# MAIN.net
KiCad netlist of a schematic drawn in EAGLE
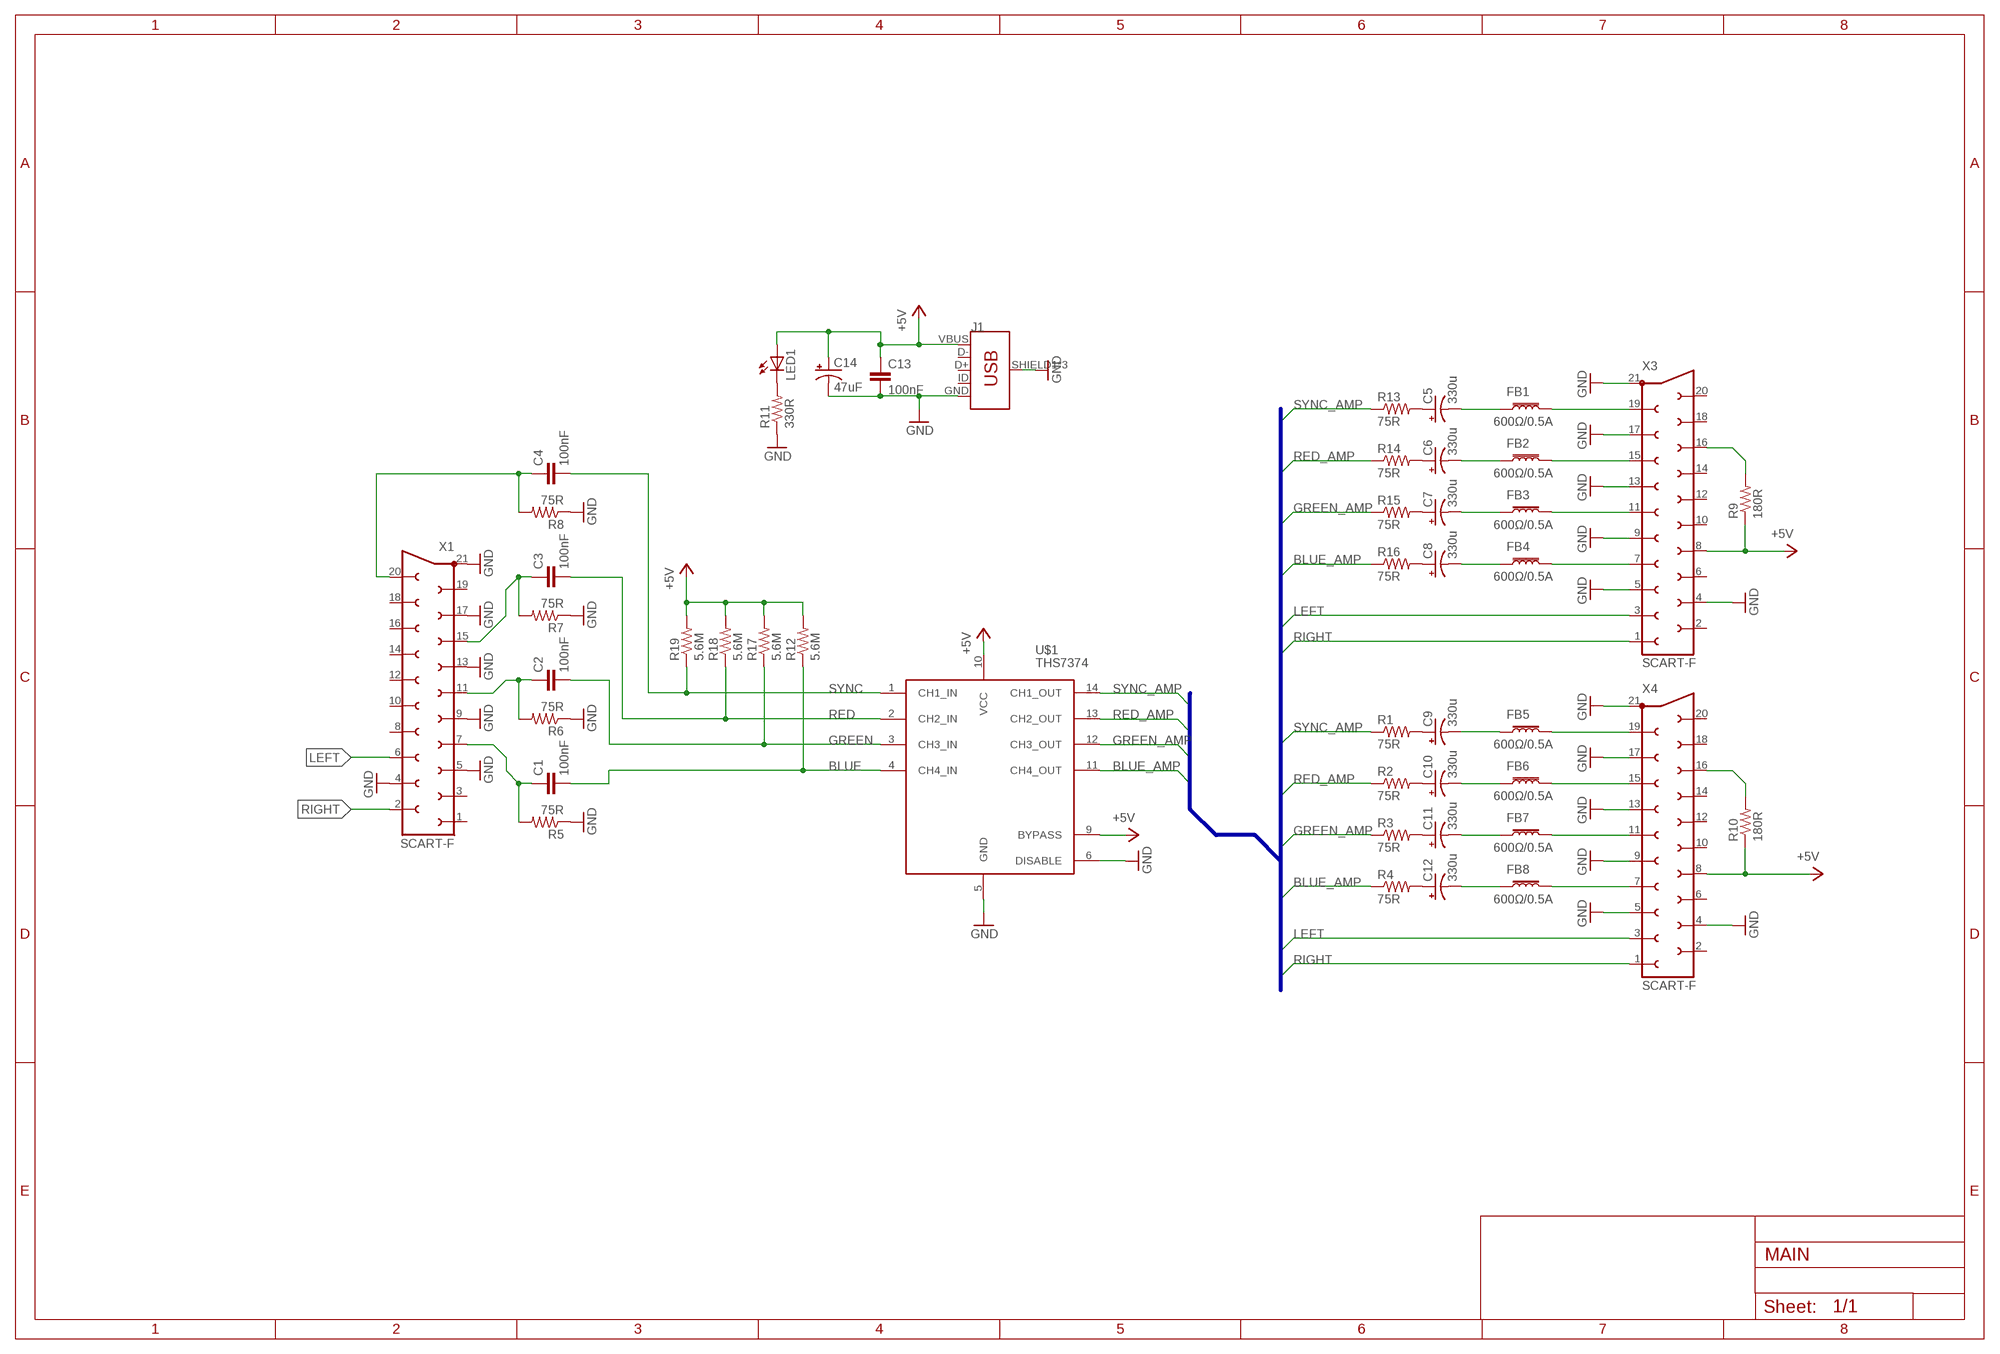
[diagram p0: schematic, sheet 1]

(export (version "E")
  (design (tool "Eeschema 10.0.6"))
  (components
    (comp (ref "C1")
      (value "100nF")
      (footprint "eagle-import:C050-025X075")
      (libsource (lib "eagle-import") (part "C-EU050-025X075"))
    )
    (comp (ref "C2")
      (value "100nF")
      (footprint "eagle-import:C050-025X075")
      (libsource (lib "eagle-import") (part "C-EU050-025X075"))
    )
    (comp (ref "C3")
      (value "100nF")
      (footprint "eagle-import:C050-025X075")
      (libsource (lib "eagle-import") (part "C-EU050-025X075"))
    )
    (comp (ref "C4")
      (value "100nF")
      (footprint "eagle-import:C050-025X075")
      (libsource (lib "eagle-import") (part "C-EU050-025X075"))
    )
    (comp (ref "C5")
      (value "330u")
      (footprint "eagle-import:E3,5-8")
      (libsource (lib "eagle-import") (part "CPOL-USE3.5-8"))
    )
    (comp (ref "C6")
      (value "330u")
      (footprint "eagle-import:E3,5-8")
      (libsource (lib "eagle-import") (part "CPOL-USE3.5-8"))
    )
    (comp (ref "C7")
      (value "330u")
      (footprint "eagle-import:E3,5-8")
      (libsource (lib "eagle-import") (part "CPOL-USE3.5-8"))
    )
    (comp (ref "C8")
      (value "330u")
      (footprint "eagle-import:E3,5-8")
      (libsource (lib "eagle-import") (part "CPOL-USE3.5-8"))
    )
    (comp (ref "C9")
      (value "330u")
      (footprint "eagle-import:E3,5-8")
      (libsource (lib "eagle-import") (part "CPOL-USE3.5-8"))
    )
    (comp (ref "C10")
      (value "330u")
      (footprint "eagle-import:E3,5-8")
      (libsource (lib "eagle-import") (part "CPOL-USE3.5-8"))
    )
    (comp (ref "C11")
      (value "330u")
      (footprint "eagle-import:E3,5-8")
      (libsource (lib "eagle-import") (part "CPOL-USE3.5-8"))
    )
    (comp (ref "C12")
      (value "330u")
      (footprint "eagle-import:E3,5-8")
      (libsource (lib "eagle-import") (part "CPOL-USE3.5-8"))
    )
    (comp (ref "C13")
      (value "100nF")
      (footprint "eagle-import:C050-025X075")
      (libsource (lib "eagle-import") (part "C-EU050-025X075"))
    )
    (comp (ref "C14")
      (value "47uF")
      (footprint "eagle-import:E3,5-8")
      (libsource (lib "eagle-import") (part "CPOL-USE3.5-8"))
    )
    (comp (ref "FB1")
      (value "600Ω/0.5A")
      (footprint "eagle-import:0603")
      (libsource (lib "eagle-import") (part "FERRITE_BEAD-0603"))
    )
    (comp (ref "FB2")
      (value "600Ω/0.5A")
      (footprint "eagle-import:0603")
      (libsource (lib "eagle-import") (part "FERRITE_BEAD-0603"))
    )
    (comp (ref "FB3")
      (value "600Ω/0.5A")
      (footprint "eagle-import:0603")
      (libsource (lib "eagle-import") (part "FERRITE_BEAD-0603"))
    )
    (comp (ref "FB4")
      (value "600Ω/0.5A")
      (footprint "eagle-import:0603")
      (libsource (lib "eagle-import") (part "FERRITE_BEAD-0603"))
    )
    (comp (ref "FB5")
      (value "600Ω/0.5A")
      (footprint "eagle-import:0603")
      (libsource (lib "eagle-import") (part "FERRITE_BEAD-0603"))
    )
    (comp (ref "FB6")
      (value "600Ω/0.5A")
      (footprint "eagle-import:0603")
      (libsource (lib "eagle-import") (part "FERRITE_BEAD-0603"))
    )
    (comp (ref "FB7")
      (value "600Ω/0.5A")
      (footprint "eagle-import:0603")
      (libsource (lib "eagle-import") (part "FERRITE_BEAD-0603"))
    )
    (comp (ref "FB8")
      (value "600Ω/0.5A")
      (footprint "eagle-import:0603")
      (libsource (lib "eagle-import") (part "FERRITE_BEAD-0603"))
    )
    (comp (ref "J1")
      (value "USB_MICRO-B_FEMALE-SMT")
      (footprint "eagle-import:USB-B-MICRO-SMD")
      (libsource (lib "eagle-import") (part "USB_MICRO-B_FEMALE-SMT"))
    )
    (comp (ref "LED1")
      (value "LED5MM")
      (footprint "eagle-import:LED5MM")
      (libsource (lib "eagle-import") (part "LED5MM"))
    )
    (comp (ref "R1")
      (value "75R")
      (footprint "eagle-import:0204_7")
      (libsource (lib "eagle-import") (part "R-US_0204/7"))
    )
    (comp (ref "R2")
      (value "75R")
      (footprint "eagle-import:0204_7")
      (libsource (lib "eagle-import") (part "R-US_0204/7"))
    )
    (comp (ref "R3")
      (value "75R")
      (footprint "eagle-import:0204_7")
      (libsource (lib "eagle-import") (part "R-US_0204/7"))
    )
    (comp (ref "R4")
      (value "75R")
      (footprint "eagle-import:0204_7")
      (libsource (lib "eagle-import") (part "R-US_0204/7"))
    )
    (comp (ref "R5")
      (value "75R")
      (footprint "eagle-import:0204_7")
      (libsource (lib "eagle-import") (part "R-US_0204/7"))
    )
    (comp (ref "R6")
      (value "75R")
      (footprint "eagle-import:0204_7")
      (libsource (lib "eagle-import") (part "R-US_0204/7"))
    )
    (comp (ref "R7")
      (value "75R")
      (footprint "eagle-import:0204_7")
      (libsource (lib "eagle-import") (part "R-US_0204/7"))
    )
    (comp (ref "R8")
      (value "75R")
      (footprint "eagle-import:0204_7")
      (libsource (lib "eagle-import") (part "R-US_0204/7"))
    )
    (comp (ref "R9")
      (value "180R")
      (footprint "eagle-import:0204_7")
      (libsource (lib "eagle-import") (part "R-US_0204/7"))
    )
    (comp (ref "R10")
      (value "180R")
      (footprint "eagle-import:0204_7")
      (libsource (lib "eagle-import") (part "R-US_0204/7"))
    )
    (comp (ref "R11")
      (value "330R")
      (footprint "eagle-import:0204_7")
      (libsource (lib "eagle-import") (part "R-US_0204/7"))
    )
    (comp (ref "R12")
      (value "5.6M")
      (footprint "eagle-import:0204_7")
      (libsource (lib "eagle-import") (part "R-US_0204/7"))
    )
    (comp (ref "R13")
      (value "75R")
      (footprint "eagle-import:0204_7")
      (libsource (lib "eagle-import") (part "R-US_0204/7"))
    )
    (comp (ref "R14")
      (value "75R")
      (footprint "eagle-import:0204_7")
      (libsource (lib "eagle-import") (part "R-US_0204/7"))
    )
    (comp (ref "R15")
      (value "75R")
      (footprint "eagle-import:0204_7")
      (libsource (lib "eagle-import") (part "R-US_0204/7"))
    )
    (comp (ref "R16")
      (value "75R")
      (footprint "eagle-import:0204_7")
      (libsource (lib "eagle-import") (part "R-US_0204/7"))
    )
    (comp (ref "R17")
      (value "5.6M")
      (footprint "eagle-import:0204_7")
      (libsource (lib "eagle-import") (part "R-US_0204/7"))
    )
    (comp (ref "R18")
      (value "5.6M")
      (footprint "eagle-import:0204_7")
      (libsource (lib "eagle-import") (part "R-US_0204/7"))
    )
    (comp (ref "R19")
      (value "5.6M")
      (footprint "eagle-import:0204_7")
      (libsource (lib "eagle-import") (part "R-US_0204/7"))
    )
    (comp (ref "U$1")
      (value "THS7374")
      (footprint "eagle-import:TSSOP-14")
      (libsource (lib "eagle-import") (part "THS7374"))
    )
    (comp (ref "X1")
      (value "SCART-F")
      (footprint "eagle-import:SCART-F")
      (libsource (lib "eagle-import") (part "SCART-F"))
    )
    (comp (ref "X3")
      (value "SCART-F")
      (footprint "eagle-import:SCART-F")
      (libsource (lib "eagle-import") (part "SCART-F"))
    )
    (comp (ref "X4")
      (value "SCART-F")
      (footprint "eagle-import:SCART-F")
      (libsource (lib "eagle-import") (part "SCART-F"))
    )
  )
  (nets
    (net (code "1") (name "+5V") (class "Default")
      (node (ref "C13") (pin "1") (pinfunction "1_1") (pintype "passive"))
      (node (ref "C14") (pin "+") (pinfunction "+_+") (pintype "passive"))
      (node (ref "J1") (pin "VBUS") (pinfunction "VBUS_VBUS") (pintype "power_in"))
      (node (ref "LED1") (pin "A") (pinfunction "A_A") (pintype "passive"))
      (node (ref "R10") (pin "1") (pinfunction "1_1") (pintype "passive"))
      (node (ref "R12") (pin "2") (pinfunction "2_2") (pintype "passive"))
      (node (ref "R17") (pin "2") (pinfunction "2_2") (pintype "passive"))
      (node (ref "R18") (pin "2") (pinfunction "2_2") (pintype "passive"))
      (node (ref "R19") (pin "2") (pinfunction "2_2") (pintype "passive"))
      (node (ref "R9") (pin "1") (pinfunction "1_1") (pintype "passive"))
      (node (ref "U$1") (pin "10") (pinfunction "VCC_10") (pintype "power_in"))
      (node (ref "U$1") (pin "9") (pinfunction "BYPASS_9") (pintype "input"))
      (node (ref "X3") (pin "8") (pinfunction "8_8") (pintype "passive"))
      (node (ref "X4") (pin "8") (pinfunction "8_8") (pintype "passive"))
    )
    (net (code "2") (name "/BLUE") (class "Default")
      (node (ref "C1") (pin "2") (pinfunction "2_2") (pintype "passive"))
      (node (ref "R12") (pin "1") (pinfunction "1_1") (pintype "passive"))
      (node (ref "U$1") (pin "4") (pinfunction "CH4_IN_4") (pintype "input"))
    )
    (net (code "3") (name "/BLUE_AMP") (class "Default")
      (node (ref "R16") (pin "1") (pinfunction "1_1") (pintype "passive"))
      (node (ref "R4") (pin "1") (pinfunction "1_1") (pintype "passive"))
      (node (ref "U$1") (pin "11") (pinfunction "CH4_OUT_11") (pintype "output"))
    )
    (net (code "4") (name "/GREEN") (class "Default")
      (node (ref "C2") (pin "2") (pinfunction "2_2") (pintype "passive"))
      (node (ref "R17") (pin "1") (pinfunction "1_1") (pintype "passive"))
      (node (ref "U$1") (pin "3") (pinfunction "CH3_IN_3") (pintype "input"))
    )
    (net (code "5") (name "/GREEN_AMP") (class "Default")
      (node (ref "R15") (pin "1") (pinfunction "1_1") (pintype "passive"))
      (node (ref "R3") (pin "1") (pinfunction "1_1") (pintype "passive"))
      (node (ref "U$1") (pin "12") (pinfunction "CH3_OUT_12") (pintype "output"))
    )
    (net (code "6") (name "/RED") (class "Default")
      (node (ref "C3") (pin "2") (pinfunction "2_2") (pintype "passive"))
      (node (ref "R18") (pin "1") (pinfunction "1_1") (pintype "passive"))
      (node (ref "U$1") (pin "2") (pinfunction "CH2_IN_2") (pintype "input"))
    )
    (net (code "7") (name "/RED_AMP") (class "Default")
      (node (ref "R14") (pin "1") (pinfunction "1_1") (pintype "passive"))
      (node (ref "R2") (pin "1") (pinfunction "1_1") (pintype "passive"))
      (node (ref "U$1") (pin "13") (pinfunction "CH2_OUT_13") (pintype "output"))
    )
    (net (code "8") (name "/SYNC") (class "Default")
      (node (ref "C4") (pin "2") (pinfunction "2_2") (pintype "passive"))
      (node (ref "R19") (pin "1") (pinfunction "1_1") (pintype "passive"))
      (node (ref "U$1") (pin "1") (pinfunction "CH1_IN_1") (pintype "input"))
    )
    (net (code "9") (name "/SYNC_AMP") (class "Default")
      (node (ref "R1") (pin "1") (pinfunction "1_1") (pintype "passive"))
      (node (ref "R13") (pin "1") (pinfunction "1_1") (pintype "passive"))
      (node (ref "U$1") (pin "14") (pinfunction "CH1_OUT_14") (pintype "output"))
    )
    (net (code "10") (name "GND") (class "Default")
      (node (ref "C13") (pin "2") (pinfunction "2_2") (pintype "passive"))
      (node (ref "C14") (pin "-") (pinfunction "-_-") (pintype "passive"))
      (node (ref "J1") (pin "GND") (pinfunction "GND_GND") (pintype "power_in"))
      (node (ref "J1") (pin "SHIELD1") (pinfunction "SHIELD_SHIELD1") (pintype "bidirectional"))
      (node (ref "J1") (pin "SHIELD2") (pinfunction "SHIELD_SHIELD2") (pintype "bidirectional"))
      (node (ref "J1") (pin "SHIELD3") (pinfunction "SHIELD_SHIELD3") (pintype "bidirectional"))
      (node (ref "R11") (pin "1") (pinfunction "1_1") (pintype "passive"))
      (node (ref "R5") (pin "1") (pinfunction "1_1") (pintype "passive"))
      (node (ref "R6") (pin "1") (pinfunction "1_1") (pintype "passive"))
      (node (ref "R7") (pin "1") (pinfunction "1_1") (pintype "passive"))
      (node (ref "R8") (pin "1") (pinfunction "1_1") (pintype "passive"))
      (node (ref "U$1") (pin "5") (pinfunction "GND_5") (pintype "power_in"))
      (node (ref "U$1") (pin "6") (pinfunction "DISABLE_6") (pintype "input"))
      (node (ref "X1") (pin "13") (pinfunction "13_13") (pintype "passive"))
      (node (ref "X1") (pin "17") (pinfunction "17_17") (pintype "passive"))
      (node (ref "X1") (pin "21") (pinfunction "21_21") (pintype "passive"))
      (node (ref "X1") (pin "4") (pinfunction "4_4") (pintype "passive"))
      (node (ref "X1") (pin "5") (pinfunction "5_5") (pintype "passive"))
      (node (ref "X1") (pin "9") (pinfunction "9_9") (pintype "passive"))
      (node (ref "X3") (pin "13") (pinfunction "13_13") (pintype "passive"))
      (node (ref "X3") (pin "17") (pinfunction "17_17") (pintype "passive"))
      (node (ref "X3") (pin "21") (pinfunction "21_21") (pintype "passive"))
      (node (ref "X3") (pin "4") (pinfunction "4_4") (pintype "passive"))
      (node (ref "X3") (pin "5") (pinfunction "5_5") (pintype "passive"))
      (node (ref "X3") (pin "9") (pinfunction "9_9") (pintype "passive"))
      (node (ref "X4") (pin "13") (pinfunction "13_13") (pintype "passive"))
      (node (ref "X4") (pin "17") (pinfunction "17_17") (pintype "passive"))
      (node (ref "X4") (pin "21") (pinfunction "21_21") (pintype "passive"))
      (node (ref "X4") (pin "4") (pinfunction "4_4") (pintype "passive"))
      (node (ref "X4") (pin "5") (pinfunction "5_5") (pintype "passive"))
      (node (ref "X4") (pin "9") (pinfunction "9_9") (pintype "passive"))
    )
    (net (code "11") (name "LEFT") (class "Default")
      (node (ref "X1") (pin "6") (pinfunction "6_6") (pintype "passive"))
      (node (ref "X3") (pin "3") (pinfunction "3_3") (pintype "passive"))
      (node (ref "X4") (pin "3") (pinfunction "3_3") (pintype "passive"))
    )
    (net (code "12") (name "Net-(C1-Pad1)") (class "Default")
      (node (ref "C1") (pin "1") (pinfunction "1_1") (pintype "passive"))
      (node (ref "R5") (pin "2") (pinfunction "2_2") (pintype "passive"))
      (node (ref "X1") (pin "7") (pinfunction "7_7") (pintype "passive"))
    )
    (net (code "13") (name "Net-(C2-Pad1)") (class "Default")
      (node (ref "C2") (pin "1") (pinfunction "1_1") (pintype "passive"))
      (node (ref "R6") (pin "2") (pinfunction "2_2") (pintype "passive"))
      (node (ref "X1") (pin "11") (pinfunction "11_11") (pintype "passive"))
    )
    (net (code "14") (name "Net-(C3-Pad1)") (class "Default")
      (node (ref "C3") (pin "1") (pinfunction "1_1") (pintype "passive"))
      (node (ref "R7") (pin "2") (pinfunction "2_2") (pintype "passive"))
      (node (ref "X1") (pin "15") (pinfunction "15_15") (pintype "passive"))
    )
    (net (code "15") (name "Net-(C4-Pad1)") (class "Default")
      (node (ref "C4") (pin "1") (pinfunction "1_1") (pintype "passive"))
      (node (ref "R8") (pin "2") (pinfunction "2_2") (pintype "passive"))
      (node (ref "X1") (pin "20") (pinfunction "20_20") (pintype "passive"))
    )
    (net (code "16") (name "Net-(C5-Pad+)") (class "Default")
      (node (ref "C5") (pin "+") (pinfunction "+_+") (pintype "passive"))
      (node (ref "R13") (pin "2") (pinfunction "2_2") (pintype "passive"))
    )
    (net (code "17") (name "Net-(C5-Pad-)") (class "Default")
      (node (ref "C5") (pin "-") (pinfunction "-_-") (pintype "passive"))
      (node (ref "FB1") (pin "1") (pinfunction "1_1") (pintype "passive"))
    )
    (net (code "18") (name "Net-(C6-Pad+)") (class "Default")
      (node (ref "C6") (pin "+") (pinfunction "+_+") (pintype "passive"))
      (node (ref "R14") (pin "2") (pinfunction "2_2") (pintype "passive"))
    )
    (net (code "19") (name "Net-(C6-Pad-)") (class "Default")
      (node (ref "C6") (pin "-") (pinfunction "-_-") (pintype "passive"))
      (node (ref "FB2") (pin "1") (pinfunction "1_1") (pintype "passive"))
    )
    (net (code "20") (name "Net-(C7-Pad+)") (class "Default")
      (node (ref "C7") (pin "+") (pinfunction "+_+") (pintype "passive"))
      (node (ref "R15") (pin "2") (pinfunction "2_2") (pintype "passive"))
    )
    (net (code "21") (name "Net-(C7-Pad-)") (class "Default")
      (node (ref "C7") (pin "-") (pinfunction "-_-") (pintype "passive"))
      (node (ref "FB3") (pin "1") (pinfunction "1_1") (pintype "passive"))
    )
    (net (code "22") (name "Net-(C8-Pad+)") (class "Default")
      (node (ref "C8") (pin "+") (pinfunction "+_+") (pintype "passive"))
      (node (ref "R16") (pin "2") (pinfunction "2_2") (pintype "passive"))
    )
    (net (code "23") (name "Net-(C8-Pad-)") (class "Default")
      (node (ref "C8") (pin "-") (pinfunction "-_-") (pintype "passive"))
      (node (ref "FB4") (pin "1") (pinfunction "1_1") (pintype "passive"))
    )
    (net (code "24") (name "Net-(C9-Pad+)") (class "Default")
      (node (ref "C9") (pin "+") (pinfunction "+_+") (pintype "passive"))
      (node (ref "R1") (pin "2") (pinfunction "2_2") (pintype "passive"))
    )
    (net (code "25") (name "Net-(C9-Pad-)") (class "Default")
      (node (ref "C9") (pin "-") (pinfunction "-_-") (pintype "passive"))
      (node (ref "FB5") (pin "1") (pinfunction "1_1") (pintype "passive"))
    )
    (net (code "26") (name "Net-(C10-Pad+)") (class "Default")
      (node (ref "C10") (pin "+") (pinfunction "+_+") (pintype "passive"))
      (node (ref "R2") (pin "2") (pinfunction "2_2") (pintype "passive"))
    )
    (net (code "27") (name "Net-(C10-Pad-)") (class "Default")
      (node (ref "C10") (pin "-") (pinfunction "-_-") (pintype "passive"))
      (node (ref "FB6") (pin "1") (pinfunction "1_1") (pintype "passive"))
    )
    (net (code "28") (name "Net-(C11-Pad+)") (class "Default")
      (node (ref "C11") (pin "+") (pinfunction "+_+") (pintype "passive"))
      (node (ref "R3") (pin "2") (pinfunction "2_2") (pintype "passive"))
    )
    (net (code "29") (name "Net-(C11-Pad-)") (class "Default")
      (node (ref "C11") (pin "-") (pinfunction "-_-") (pintype "passive"))
      (node (ref "FB7") (pin "1") (pinfunction "1_1") (pintype "passive"))
    )
    (net (code "30") (name "Net-(C12-Pad+)") (class "Default")
      (node (ref "C12") (pin "+") (pinfunction "+_+") (pintype "passive"))
      (node (ref "R4") (pin "2") (pinfunction "2_2") (pintype "passive"))
    )
    (net (code "31") (name "Net-(C12-Pad-)") (class "Default")
      (node (ref "C12") (pin "-") (pinfunction "-_-") (pintype "passive"))
      (node (ref "FB8") (pin "1") (pinfunction "1_1") (pintype "passive"))
    )
    (net (code "32") (name "Net-(FB1-Pad2)") (class "Default")
      (node (ref "FB1") (pin "2") (pinfunction "2_2") (pintype "passive"))
      (node (ref "X3") (pin "19") (pinfunction "19_19") (pintype "passive"))
    )
    (net (code "33") (name "Net-(FB2-Pad2)") (class "Default")
      (node (ref "FB2") (pin "2") (pinfunction "2_2") (pintype "passive"))
      (node (ref "X3") (pin "15") (pinfunction "15_15") (pintype "passive"))
    )
    (net (code "34") (name "Net-(FB3-Pad2)") (class "Default")
      (node (ref "FB3") (pin "2") (pinfunction "2_2") (pintype "passive"))
      (node (ref "X3") (pin "11") (pinfunction "11_11") (pintype "passive"))
    )
    (net (code "35") (name "Net-(FB4-Pad2)") (class "Default")
      (node (ref "FB4") (pin "2") (pinfunction "2_2") (pintype "passive"))
      (node (ref "X3") (pin "7") (pinfunction "7_7") (pintype "passive"))
    )
    (net (code "36") (name "Net-(FB5-Pad2)") (class "Default")
      (node (ref "FB5") (pin "2") (pinfunction "2_2") (pintype "passive"))
      (node (ref "X4") (pin "19") (pinfunction "19_19") (pintype "passive"))
    )
    (net (code "37") (name "Net-(FB6-Pad2)") (class "Default")
      (node (ref "FB6") (pin "2") (pinfunction "2_2") (pintype "passive"))
      (node (ref "X4") (pin "15") (pinfunction "15_15") (pintype "passive"))
    )
    (net (code "38") (name "Net-(FB7-Pad2)") (class "Default")
      (node (ref "FB7") (pin "2") (pinfunction "2_2") (pintype "passive"))
      (node (ref "X4") (pin "11") (pinfunction "11_11") (pintype "passive"))
    )
    (net (code "39") (name "Net-(FB8-Pad2)") (class "Default")
      (node (ref "FB8") (pin "2") (pinfunction "2_2") (pintype "passive"))
      (node (ref "X4") (pin "7") (pinfunction "7_7") (pintype "passive"))
    )
    (net (code "40") (name "Net-(LED1-C)") (class "Default")
      (node (ref "LED1") (pin "K") (pinfunction "C_K") (pintype "passive"))
      (node (ref "R11") (pin "2") (pinfunction "2_2") (pintype "passive"))
    )
    (net (code "41") (name "Net-(R9-Pad2)") (class "Default")
      (node (ref "R9") (pin "2") (pinfunction "2_2") (pintype "passive"))
      (node (ref "X3") (pin "16") (pinfunction "16_16") (pintype "passive"))
    )
    (net (code "42") (name "Net-(R10-Pad2)") (class "Default")
      (node (ref "R10") (pin "2") (pinfunction "2_2") (pintype "passive"))
      (node (ref "X4") (pin "16") (pinfunction "16_16") (pintype "passive"))
    )
    (net (code "43") (name "RIGHT") (class "Default")
      (node (ref "X1") (pin "2") (pinfunction "2_2") (pintype "passive"))
      (node (ref "X3") (pin "1") (pinfunction "1_1") (pintype "passive"))
      (node (ref "X4") (pin "1") (pinfunction "1_1") (pintype "passive"))
    )
    (net (code "44") (name "unconnected-(J1-PadD+)") (class "Default")
      (node (ref "J1") (pin "D+") (pinfunction "D+_D+") (pintype "bidirectional"))
    )
    (net (code "45") (name "unconnected-(J1-PadD-)") (class "Default")
      (node (ref "J1") (pin "D-") (pinfunction "D-_D-") (pintype "bidirectional"))
    )
    (net (code "46") (name "unconnected-(J1-PadID)") (class "Default")
      (node (ref "J1") (pin "ID") (pinfunction "ID_ID") (pintype "bidirectional"))
    )
    (net (code "47") (name "unconnected-(X1-Pad1)") (class "Default")
      (node (ref "X1") (pin "1") (pinfunction "1_1") (pintype "passive"))
    )
    (net (code "48") (name "unconnected-(X1-Pad3)") (class "Default")
      (node (ref "X1") (pin "3") (pinfunction "3_3") (pintype "passive"))
    )
    (net (code "49") (name "unconnected-(X1-Pad8)") (class "Default")
      (node (ref "X1") (pin "8") (pinfunction "8_8") (pintype "passive"))
    )
    (net (code "50") (name "unconnected-(X1-Pad10)") (class "Default")
      (node (ref "X1") (pin "10") (pinfunction "10_10") (pintype "passive"))
    )
    (net (code "51") (name "unconnected-(X1-Pad12)") (class "Default")
      (node (ref "X1") (pin "12") (pinfunction "12_12") (pintype "passive"))
    )
    (net (code "52") (name "unconnected-(X1-Pad14)") (class "Default")
      (node (ref "X1") (pin "14") (pinfunction "14_14") (pintype "passive"))
    )
    (net (code "53") (name "unconnected-(X1-Pad16)") (class "Default")
      (node (ref "X1") (pin "16") (pinfunction "16_16") (pintype "passive"))
    )
    (net (code "54") (name "unconnected-(X1-Pad18)") (class "Default")
      (node (ref "X1") (pin "18") (pinfunction "18_18") (pintype "passive"))
    )
    (net (code "55") (name "unconnected-(X1-Pad19)") (class "Default")
      (node (ref "X1") (pin "19") (pinfunction "19_19") (pintype "passive"))
    )
    (net (code "56") (name "unconnected-(X3-Pad2)") (class "Default")
      (node (ref "X3") (pin "2") (pinfunction "2_2") (pintype "passive"))
    )
    (net (code "57") (name "unconnected-(X3-Pad6)") (class "Default")
      (node (ref "X3") (pin "6") (pinfunction "6_6") (pintype "passive"))
    )
    (net (code "58") (name "unconnected-(X3-Pad10)") (class "Default")
      (node (ref "X3") (pin "10") (pinfunction "10_10") (pintype "passive"))
    )
    (net (code "59") (name "unconnected-(X3-Pad12)") (class "Default")
      (node (ref "X3") (pin "12") (pinfunction "12_12") (pintype "passive"))
    )
    (net (code "60") (name "unconnected-(X3-Pad14)") (class "Default")
      (node (ref "X3") (pin "14") (pinfunction "14_14") (pintype "passive"))
    )
    (net (code "61") (name "unconnected-(X3-Pad18)") (class "Default")
      (node (ref "X3") (pin "18") (pinfunction "18_18") (pintype "passive"))
    )
    (net (code "62") (name "unconnected-(X3-Pad20)") (class "Default")
      (node (ref "X3") (pin "20") (pinfunction "20_20") (pintype "passive"))
    )
    (net (code "63") (name "unconnected-(X4-Pad2)") (class "Default")
      (node (ref "X4") (pin "2") (pinfunction "2_2") (pintype "passive"))
    )
    (net (code "64") (name "unconnected-(X4-Pad6)") (class "Default")
      (node (ref "X4") (pin "6") (pinfunction "6_6") (pintype "passive"))
    )
    (net (code "65") (name "unconnected-(X4-Pad10)") (class "Default")
      (node (ref "X4") (pin "10") (pinfunction "10_10") (pintype "passive"))
    )
    (net (code "66") (name "unconnected-(X4-Pad12)") (class "Default")
      (node (ref "X4") (pin "12") (pinfunction "12_12") (pintype "passive"))
    )
    (net (code "67") (name "unconnected-(X4-Pad14)") (class "Default")
      (node (ref "X4") (pin "14") (pinfunction "14_14") (pintype "passive"))
    )
    (net (code "68") (name "unconnected-(X4-Pad18)") (class "Default")
      (node (ref "X4") (pin "18") (pinfunction "18_18") (pintype "passive"))
    )
    (net (code "69") (name "unconnected-(X4-Pad20)") (class "Default")
      (node (ref "X4") (pin "20") (pinfunction "20_20") (pintype "passive"))
    )
  )
)
